# main.net
KiCad netlist of a schematic drawn in Altium Designer
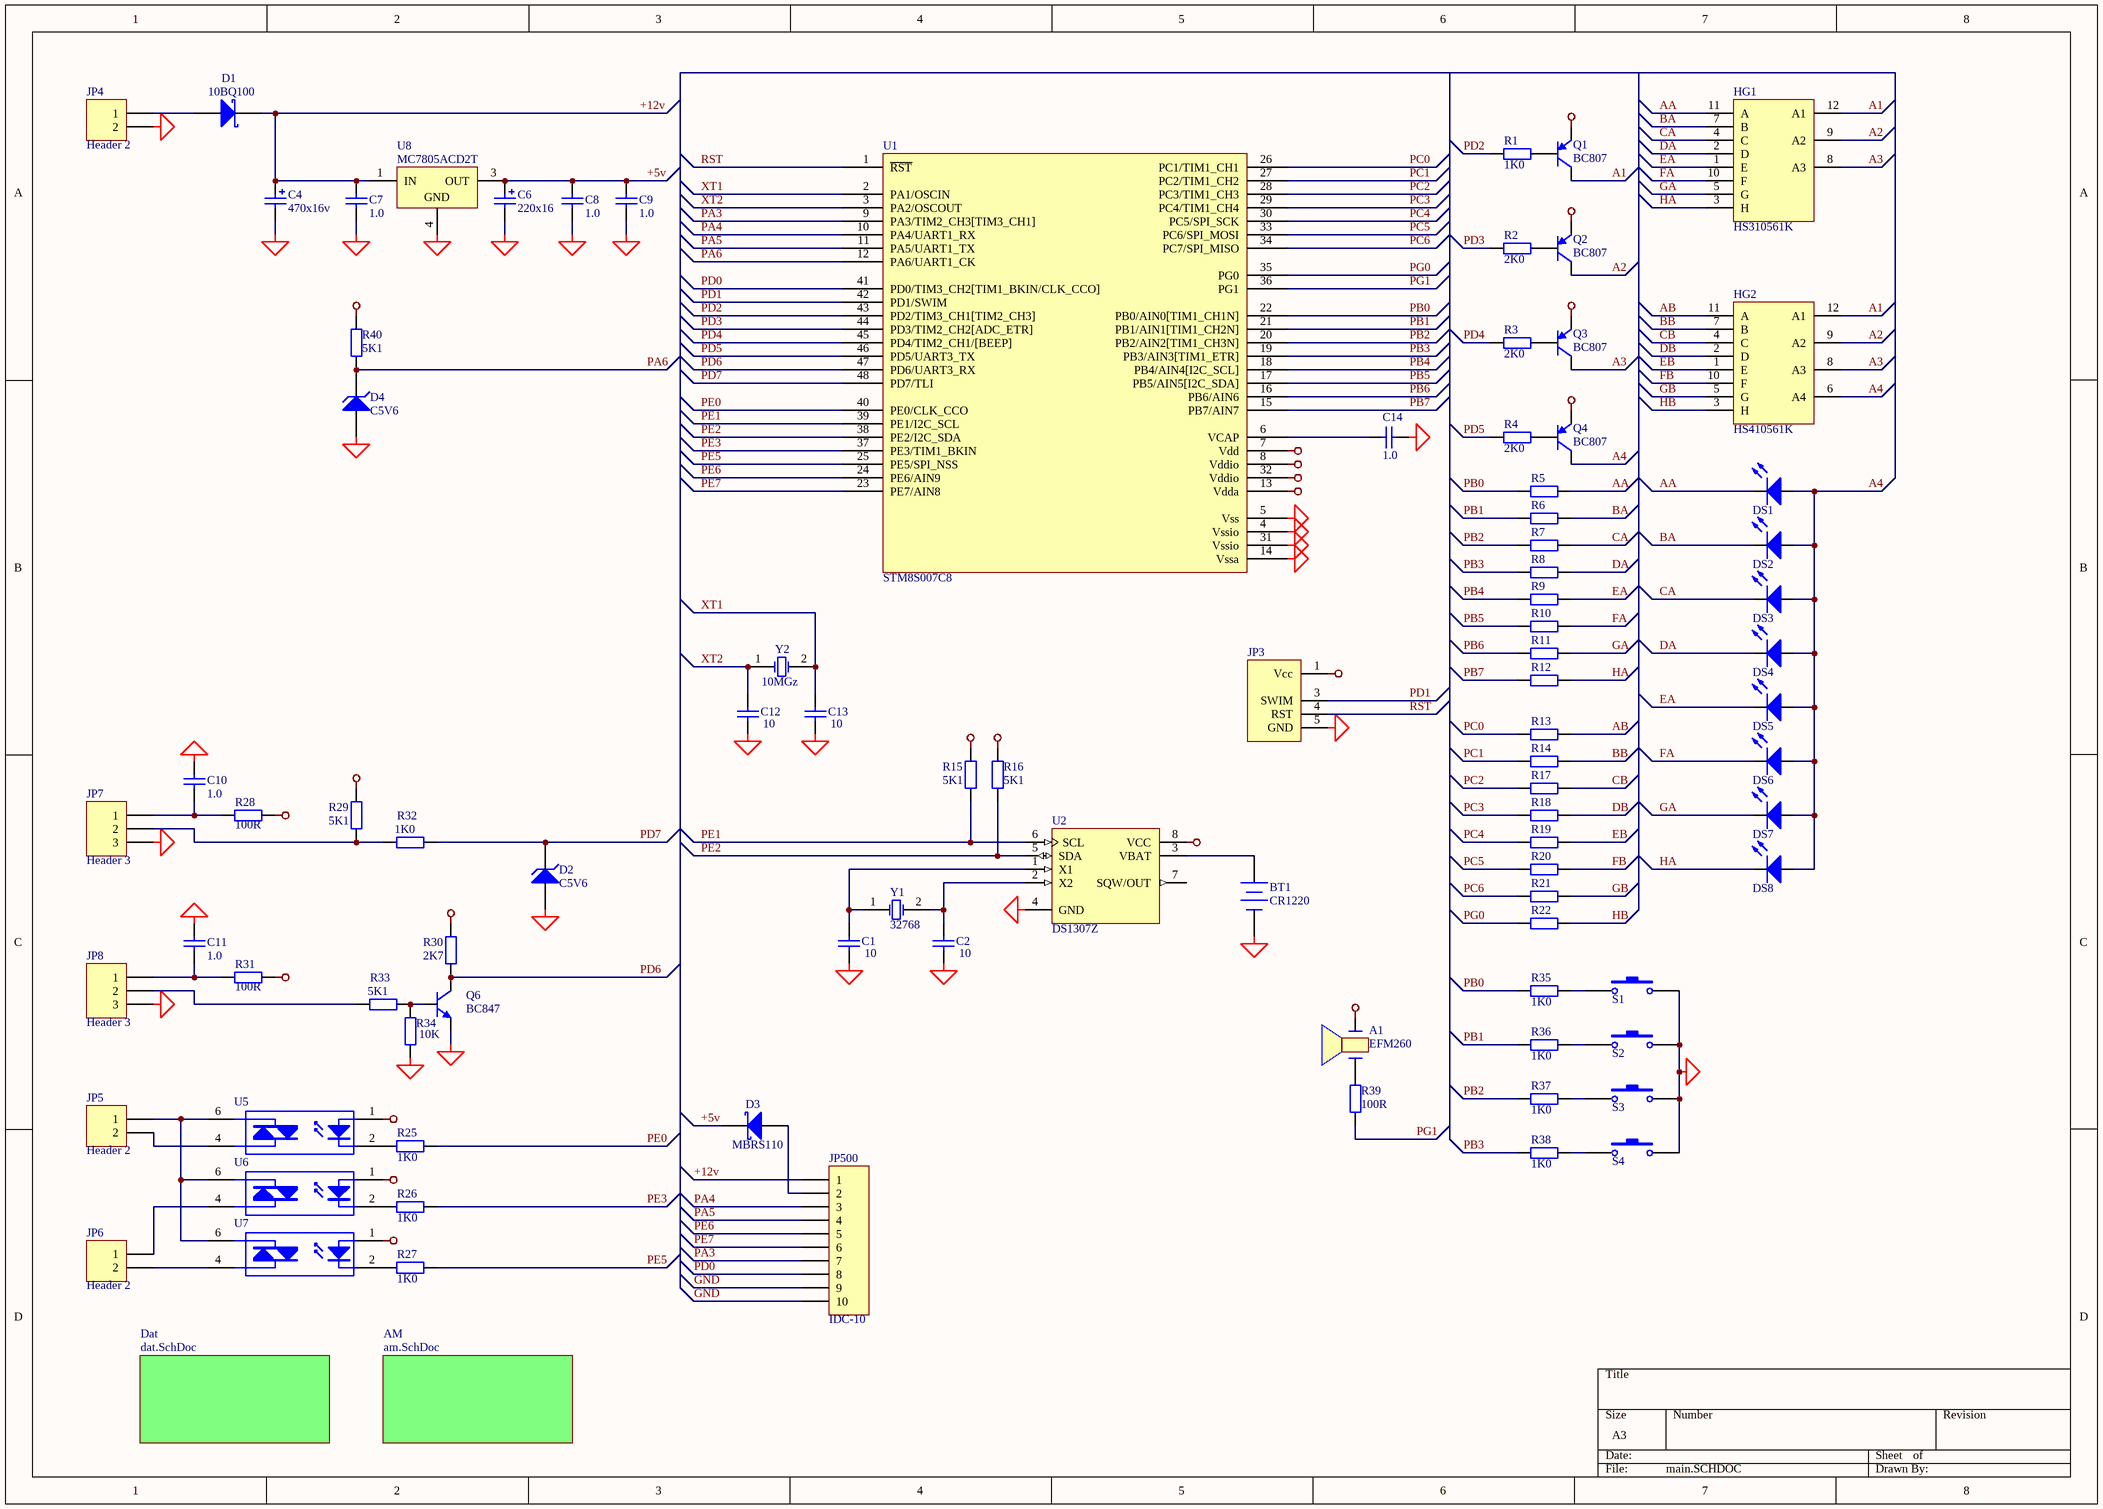
[diagram p0: main.SCHDOC]

(export (version "E")
  (design (tool "Eeschema 10.0.6"))
  (components
    (comp (ref "A1")
      (value "EFM260")
      (footprint "zumm")
      (description "Beeper")
      (libsource (lib "PAL") (part "PJEZ0"))
    )
    (comp (ref "BT1")
      (value "CR1220")
      (footprint "1220_holder")
      (description "Multicell Battery")
      (fields (field (name "MANUFACTURER") "Generic Components") (field (name "PUBLISHER") "Altium Limited"))
      (libsource (lib "Miscellaneous Devices") (part "Battery"))
    )
    (comp (ref "C1")
      (value "10")
      (footprint "_1206")
      (description "Capacitor")
      (fields (field (name "MANUFACTURER") "Generic Components") (field (name "PUBLISHER") "Altium Limited"))
      (libsource (lib "Miscellaneous Devices") (part "Cap Semi"))
    )
    (comp (ref "C2")
      (value "10")
      (footprint "_1206")
      (description "Capacitor")
      (fields (field (name "MANUFACTURER") "Generic Components") (field (name "PUBLISHER") "Altium Limited"))
      (libsource (lib "Miscellaneous Devices") (part "Cap Semi"))
    )
    (comp (ref "C4")
      (value "470x16v")
      (footprint "el5")
      (description "Polarized Capacitor (Radial)")
      (fields (field (name "MANUFACTURER") "Generic Components") (field (name "PUBLISHER") "Altium Limited"))
      (libsource (lib "BUF") (part "Cap Pol1"))
    )
    (comp (ref "C6")
      (value "220x16")
      (footprint "el3")
      (description "Polarized Capacitor (Radial)")
      (fields (field (name "MANUFACTURER") "Generic Components") (field (name "PUBLISHER") "Altium Limited"))
      (libsource (lib "BUF") (part "Cap Pol"))
    )
    (comp (ref "C7")
      (value "Cap")
      (footprint "_1206")
      (description "Capacitor")
      (fields
        (field (name "MANUFACTURER") "Generic Components")
        (field (name "ALTIUM_VALUE") "1.0")
        (field (name "PUBLISHER") "Altium Limited")
      )
      (libsource (lib "BUF") (part "Cap"))
    )
    (comp (ref "C8")
      (value "Cap")
      (footprint "_1206")
      (description "Capacitor")
      (fields
        (field (name "MANUFACTURER") "Generic Components")
        (field (name "ALTIUM_VALUE") "1.0")
        (field (name "PUBLISHER") "Altium Limited")
      )
      (libsource (lib "BUF") (part "Cap"))
    )
    (comp (ref "C9")
      (value "Cap")
      (footprint "_1206")
      (description "Capacitor")
      (fields
        (field (name "MANUFACTURER") "Generic Components")
        (field (name "ALTIUM_VALUE") "1.0")
        (field (name "PUBLISHER") "Altium Limited")
      )
      (libsource (lib "BUF") (part "Cap"))
    )
    (comp (ref "C10")
      (value "Cap")
      (footprint "_1206")
      (description "Capacitor")
      (fields
        (field (name "MANUFACTURER") "Generic Components")
        (field (name "ALTIUM_VALUE") "1.0")
        (field (name "PUBLISHER") "Altium Limited")
      )
      (libsource (lib "BUF") (part "Cap"))
    )
    (comp (ref "C11")
      (value "Cap")
      (footprint "_1206")
      (description "Capacitor")
      (fields
        (field (name "MANUFACTURER") "Generic Components")
        (field (name "ALTIUM_VALUE") "1.0")
        (field (name "PUBLISHER") "Altium Limited")
      )
      (libsource (lib "BUF") (part "Cap"))
    )
    (comp (ref "C12")
      (value "10")
      (footprint "_1206")
      (description "Capacitor")
      (fields (field (name "MANUFACTURER") "Generic Components") (field (name "PUBLISHER") "Altium Limited"))
      (libsource (lib "Miscellaneous Devices") (part "Cap Semi"))
    )
    (comp (ref "C13")
      (value "10")
      (footprint "_1206")
      (description "Capacitor")
      (fields (field (name "MANUFACTURER") "Generic Components") (field (name "PUBLISHER") "Altium Limited"))
      (libsource (lib "Miscellaneous Devices") (part "Cap Semi"))
    )
    (comp (ref "C14")
      (value "1.0")
      (footprint "_1206")
      (description "Capacitor")
      (fields (field (name "MANUFACTURER") "Generic Components") (field (name "PUBLISHER") "Altium Limited"))
      (libsource (lib "Miscellaneous Devices") (part "Cap Semi"))
    )
    (comp (ref "D1")
      (value "10BQ100")
      (footprint "DSO-C2/X2.3")
      (description "Schottky Rectifier")
      (fields
        (field (name "MANUFACTURER") "International Rectifier")
        (field (name "PUBLISHER") "Altium Limited")
      )
      (libsource (lib "IR Discrete Diode") (part "10BQ015"))
    )
    (comp (ref "D2")
      (value "C5V6")
      (footprint "_1206d")
      (description "Zener Diode")
      (fields (field (name "MANUFACTURER") "Generic Components") (field (name "PUBLISHER") "Altium Limited"))
      (libsource (lib "Miscellaneous Devices") (part "D Zener"))
    )
    (comp (ref "D3")
      (value "MBRS110")
      (footprint "DSO-C2/X2.3")
      (description "Schottky Rectifier")
      (fields
        (field (name "MANUFACTURER") "International Rectifier")
        (field (name "PUBLISHER") "Altium Limited")
      )
      (libsource (lib "IR Discrete Diode") (part "10BQ015"))
    )
    (comp (ref "D4")
      (value "C5V6")
      (footprint "_1206d")
      (description "Zener Diode")
      (fields (field (name "MANUFACTURER") "Generic Components") (field (name "PUBLISHER") "Altium Limited"))
      (libsource (lib "Miscellaneous Devices") (part "D Zener"))
    )
    (comp (ref "DS1")
      (value "LED0")
      (footprint "el3")
      (description "Typical INFRARED GaAs LED")
      (fields (field (name "MANUFACTURER") "Generic Components") (field (name "PUBLISHER") "Altium Limited"))
      (libsource (lib "PAL") (part "LED0"))
    )
    (comp (ref "DS2")
      (value "LED0")
      (footprint "el3")
      (description "Typical INFRARED GaAs LED")
      (fields (field (name "MANUFACTURER") "Generic Components") (field (name "PUBLISHER") "Altium Limited"))
      (libsource (lib "PAL") (part "LED0"))
    )
    (comp (ref "DS3")
      (value "LED0")
      (footprint "el3")
      (description "Typical INFRARED GaAs LED")
      (fields (field (name "MANUFACTURER") "Generic Components") (field (name "PUBLISHER") "Altium Limited"))
      (libsource (lib "PAL") (part "LED0"))
    )
    (comp (ref "DS4")
      (value "LED0")
      (footprint "el3")
      (description "Typical INFRARED GaAs LED")
      (fields (field (name "MANUFACTURER") "Generic Components") (field (name "PUBLISHER") "Altium Limited"))
      (libsource (lib "PAL") (part "LED0"))
    )
    (comp (ref "DS5")
      (value "LED0")
      (footprint "el3")
      (description "Typical INFRARED GaAs LED")
      (fields (field (name "MANUFACTURER") "Generic Components") (field (name "PUBLISHER") "Altium Limited"))
      (libsource (lib "PAL") (part "LED0"))
    )
    (comp (ref "DS6")
      (value "LED0")
      (footprint "el3")
      (description "Typical INFRARED GaAs LED")
      (fields (field (name "MANUFACTURER") "Generic Components") (field (name "PUBLISHER") "Altium Limited"))
      (libsource (lib "PAL") (part "LED0"))
    )
    (comp (ref "DS7")
      (value "LED0")
      (footprint "el3")
      (description "Typical INFRARED GaAs LED")
      (fields (field (name "MANUFACTURER") "Generic Components") (field (name "PUBLISHER") "Altium Limited"))
      (libsource (lib "PAL") (part "LED0"))
    )
    (comp (ref "DS8")
      (value "LED0")
      (footprint "el3")
      (description "Typical INFRARED GaAs LED")
      (fields (field (name "MANUFACTURER") "Generic Components") (field (name "PUBLISHER") "Altium Limited"))
      (libsource (lib "PAL") (part "LED0"))
    )
    (comp (ref "HG1") (value "HS310561K") (footprint "HS310561K") (libsource (lib "PAL") (part "HS310561K")))
    (comp (ref "HG2") (value "HS410561K") (footprint "HS410561K") (libsource (lib "PAL") (part "HS410561K")))
    (comp (ref "JP3") (value "~") (footprint "HDR1X5_uart") (libsource (lib "PAL") (part "SWIM_CONN")))
    (comp (ref "JP4")
      (value "Header 2")
      (footprint "BT5-2")
      (description "Header, 2-Pin")
      (fields (field (name "MANUFACTURER") "Generic Components") (field (name "PUBLISHER") "Altium Limited"))
      (libsource (lib "Miscellaneous Connectors") (part "Header 2"))
    )
    (comp (ref "JP5")
      (value "Header 2")
      (footprint "BT5-2")
      (description "Header, 2-Pin")
      (fields (field (name "MANUFACTURER") "Generic Components") (field (name "PUBLISHER") "Altium Limited"))
      (libsource (lib "Miscellaneous Connectors") (part "Header 2"))
    )
    (comp (ref "JP6")
      (value "Header 2")
      (footprint "BT5-2")
      (description "Header, 2-Pin")
      (fields (field (name "MANUFACTURER") "Generic Components") (field (name "PUBLISHER") "Altium Limited"))
      (libsource (lib "Miscellaneous Connectors") (part "Header 2"))
    )
    (comp (ref "JP7")
      (value "Header 3")
      (footprint "BT5-3")
      (description "Header, 3-Pin")
      (fields (field (name "MANUFACTURER") "Generic Components") (field (name "PUBLISHER") "Altium Limited"))
      (libsource (lib "Miscellaneous Connectors") (part "Header 3"))
    )
    (comp (ref "JP8")
      (value "Header 3")
      (footprint "BT5-3")
      (description "Header, 3-Pin")
      (fields (field (name "MANUFACTURER") "Generic Components") (field (name "PUBLISHER") "Altium Limited"))
      (libsource (lib "Miscellaneous Connectors") (part "Header 3"))
    )
    (comp (ref "JP500")
      (value "IDC-10")
      (footprint "HDR2X5")
      (description "Header, 10-Pin")
      (fields (field (name "MANUFACTURER") "Generic Components") (field (name "PUBLISHER") "Altium Limited"))
      (libsource (lib "Miscellaneous Connectors") (part "Header 10"))
    )
    (comp (ref "Q1")
      (value "BC807")
      (footprint "SO-G3")
      (description "General Purpose Transistor PNP Silicon")
      (fields (field (name "MANUFACTURER") "Motorola") (field (name "PUBLISHER") "Altium Limited"))
      (libsource (lib "PAL") (part "BC857ALT1"))
    )
    (comp (ref "Q2")
      (value "BC807")
      (footprint "SO-G3")
      (description "General Purpose Transistor PNP Silicon")
      (fields (field (name "MANUFACTURER") "Motorola") (field (name "PUBLISHER") "Altium Limited"))
      (libsource (lib "PAL") (part "BC857ALT1"))
    )
    (comp (ref "Q3")
      (value "BC807")
      (footprint "SO-G3")
      (description "General Purpose Transistor PNP Silicon")
      (fields (field (name "MANUFACTURER") "Motorola") (field (name "PUBLISHER") "Altium Limited"))
      (libsource (lib "PAL") (part "BC857ALT1"))
    )
    (comp (ref "Q4")
      (value "BC807")
      (footprint "SO-G3")
      (description "General Purpose Transistor PNP Silicon")
      (fields (field (name "MANUFACTURER") "Motorola") (field (name "PUBLISHER") "Altium Limited"))
      (libsource (lib "PAL") (part "BC857ALT1"))
    )
    (comp (ref "Q6")
      (value "BC847")
      (footprint "SO-G3")
      (description "General Purpose Transistor NPN Silicon")
      (fields (field (name "MANUFACTURER") "Motorola") (field (name "PUBLISHER") "Altium Limited"))
      (libsource (lib "PAL") (part "BC847ALT1"))
    )
    (comp (ref "R1")
      (value "Res2")
      (footprint "_1206")
      (description "Resistor")
      (fields
        (field (name "MANUFACTURER") "Generic Components")
        (field (name "ALTIUM_VALUE") "1K0")
        (field (name "PUBLISHER") "Altium Limited")
      )
      (libsource (lib "") (part "Res2_1"))
    )
    (comp (ref "R2")
      (value "Res2")
      (footprint "_1206")
      (description "Resistor")
      (fields
        (field (name "MANUFACTURER") "Generic Components")
        (field (name "ALTIUM_VALUE") "2K0")
        (field (name "PUBLISHER") "Altium Limited")
      )
      (libsource (lib "") (part "Res2_1"))
    )
    (comp (ref "R3")
      (value "Res2")
      (footprint "_1206")
      (description "Resistor")
      (fields
        (field (name "MANUFACTURER") "Generic Components")
        (field (name "ALTIUM_VALUE") "2K0")
        (field (name "PUBLISHER") "Altium Limited")
      )
      (libsource (lib "") (part "Res2_1"))
    )
    (comp (ref "R4")
      (value "Res2")
      (footprint "_1206")
      (description "Resistor")
      (fields
        (field (name "MANUFACTURER") "Generic Components")
        (field (name "ALTIUM_VALUE") "2K0")
        (field (name "PUBLISHER") "Altium Limited")
      )
      (libsource (lib "") (part "Res2_1"))
    )
    (comp (ref "R5")
      (value "Res2")
      (footprint "_1206")
      (description "Resistor")
      (fields (field (name "MANUFACTURER") "Generic Components") (field (name "PUBLISHER") "Altium Limited"))
      (libsource (lib "") (part "Res2_1"))
    )
    (comp (ref "R6")
      (value "Res2")
      (footprint "_1206")
      (description "Resistor")
      (fields (field (name "MANUFACTURER") "Generic Components") (field (name "PUBLISHER") "Altium Limited"))
      (libsource (lib "") (part "Res2_1"))
    )
    (comp (ref "R7")
      (value "Res2")
      (footprint "_1206")
      (description "Resistor")
      (fields (field (name "MANUFACTURER") "Generic Components") (field (name "PUBLISHER") "Altium Limited"))
      (libsource (lib "") (part "Res2_1"))
    )
    (comp (ref "R8")
      (value "Res2")
      (footprint "_1206")
      (description "Resistor")
      (fields (field (name "MANUFACTURER") "Generic Components") (field (name "PUBLISHER") "Altium Limited"))
      (libsource (lib "") (part "Res2_1"))
    )
    (comp (ref "R9")
      (value "Res2")
      (footprint "_1206")
      (description "Resistor")
      (fields (field (name "MANUFACTURER") "Generic Components") (field (name "PUBLISHER") "Altium Limited"))
      (libsource (lib "") (part "Res2_1"))
    )
    (comp (ref "R10")
      (value "Res2")
      (footprint "_1206")
      (description "Resistor")
      (fields (field (name "MANUFACTURER") "Generic Components") (field (name "PUBLISHER") "Altium Limited"))
      (libsource (lib "") (part "Res2_1"))
    )
    (comp (ref "R11")
      (value "Res2")
      (footprint "_1206")
      (description "Resistor")
      (fields (field (name "MANUFACTURER") "Generic Components") (field (name "PUBLISHER") "Altium Limited"))
      (libsource (lib "") (part "Res2_1"))
    )
    (comp (ref "R12")
      (value "Res2")
      (footprint "_1206")
      (description "Resistor")
      (fields (field (name "MANUFACTURER") "Generic Components") (field (name "PUBLISHER") "Altium Limited"))
      (libsource (lib "") (part "Res2_1"))
    )
    (comp (ref "R13")
      (value "Res2")
      (footprint "_1206")
      (description "Resistor")
      (fields (field (name "MANUFACTURER") "Generic Components") (field (name "PUBLISHER") "Altium Limited"))
      (libsource (lib "") (part "Res2_1"))
    )
    (comp (ref "R14")
      (value "Res2")
      (footprint "_1206")
      (description "Resistor")
      (fields (field (name "MANUFACTURER") "Generic Components") (field (name "PUBLISHER") "Altium Limited"))
      (libsource (lib "") (part "Res2_1"))
    )
    (comp (ref "R15")
      (value "Res2")
      (footprint "_1206")
      (description "Resistor")
      (fields
        (field (name "MANUFACTURER") "Generic Components")
        (field (name "ALTIUM_VALUE") "5K1")
        (field (name "PUBLISHER") "Altium Limited")
      )
      (libsource (lib "Miscellaneous Devices") (part "Res2"))
    )
    (comp (ref "R16")
      (value "Res2")
      (footprint "_1206")
      (description "Resistor")
      (fields
        (field (name "MANUFACTURER") "Generic Components")
        (field (name "ALTIUM_VALUE") "5K1")
        (field (name "PUBLISHER") "Altium Limited")
      )
      (libsource (lib "Miscellaneous Devices") (part "Res2"))
    )
    (comp (ref "R17")
      (value "Res2")
      (footprint "_1206")
      (description "Resistor")
      (fields (field (name "MANUFACTURER") "Generic Components") (field (name "PUBLISHER") "Altium Limited"))
      (libsource (lib "") (part "Res2_1"))
    )
    (comp (ref "R18")
      (value "Res2")
      (footprint "_1206")
      (description "Resistor")
      (fields (field (name "MANUFACTURER") "Generic Components") (field (name "PUBLISHER") "Altium Limited"))
      (libsource (lib "") (part "Res2_1"))
    )
    (comp (ref "R19")
      (value "Res2")
      (footprint "_1206")
      (description "Resistor")
      (fields (field (name "MANUFACTURER") "Generic Components") (field (name "PUBLISHER") "Altium Limited"))
      (libsource (lib "") (part "Res2_1"))
    )
    (comp (ref "R20")
      (value "Res2")
      (footprint "_1206")
      (description "Resistor")
      (fields (field (name "MANUFACTURER") "Generic Components") (field (name "PUBLISHER") "Altium Limited"))
      (libsource (lib "") (part "Res2_1"))
    )
    (comp (ref "R21")
      (value "Res2")
      (footprint "_1206")
      (description "Resistor")
      (fields (field (name "MANUFACTURER") "Generic Components") (field (name "PUBLISHER") "Altium Limited"))
      (libsource (lib "") (part "Res2_1"))
    )
    (comp (ref "R22")
      (value "Res2")
      (footprint "_1206")
      (description "Resistor")
      (fields (field (name "MANUFACTURER") "Generic Components") (field (name "PUBLISHER") "Altium Limited"))
      (libsource (lib "") (part "Res2_1"))
    )
    (comp (ref "R25")
      (value "Res2")
      (footprint "_1206")
      (description "Resistor")
      (fields
        (field (name "MANUFACTURER") "Generic Components")
        (field (name "ALTIUM_VALUE") "1K0")
        (field (name "PUBLISHER") "Altium Limited")
      )
      (libsource (lib "") (part "Res2_2"))
    )
    (comp (ref "R26")
      (value "Res2")
      (footprint "_1206")
      (description "Resistor")
      (fields
        (field (name "MANUFACTURER") "Generic Components")
        (field (name "ALTIUM_VALUE") "1K0")
        (field (name "PUBLISHER") "Altium Limited")
      )
      (libsource (lib "") (part "Res2_2"))
    )
    (comp (ref "R27")
      (value "Res2")
      (footprint "_1206")
      (description "Resistor")
      (fields
        (field (name "MANUFACTURER") "Generic Components")
        (field (name "ALTIUM_VALUE") "1K0")
        (field (name "PUBLISHER") "Altium Limited")
      )
      (libsource (lib "") (part "Res2_2"))
    )
    (comp (ref "R28")
      (value "Res2")
      (footprint "_1206")
      (description "Resistor")
      (fields
        (field (name "MANUFACTURER") "Generic Components")
        (field (name "ALTIUM_VALUE") "100R")
        (field (name "PUBLISHER") "Altium Limited")
      )
      (libsource (lib "") (part "Res2_2"))
    )
    (comp (ref "R29")
      (value "Res2")
      (footprint "_1206")
      (description "Resistor")
      (fields
        (field (name "MANUFACTURER") "Generic Components")
        (field (name "ALTIUM_VALUE") "5K1")
        (field (name "PUBLISHER") "Altium Limited")
      )
      (libsource (lib "Miscellaneous Devices") (part "Res2"))
    )
    (comp (ref "R30")
      (value "Res2")
      (footprint "_1206")
      (description "Resistor")
      (fields
        (field (name "MANUFACTURER") "Generic Components")
        (field (name "ALTIUM_VALUE") "2K7")
        (field (name "PUBLISHER") "Altium Limited")
      )
      (libsource (lib "Miscellaneous Devices") (part "Res2"))
    )
    (comp (ref "R31")
      (value "Res2")
      (footprint "_1206")
      (description "Resistor")
      (fields
        (field (name "MANUFACTURER") "Generic Components")
        (field (name "ALTIUM_VALUE") "100R")
        (field (name "PUBLISHER") "Altium Limited")
      )
      (libsource (lib "") (part "Res2_2"))
    )
    (comp (ref "R32")
      (value "1K0")
      (footprint "_1206")
      (description "Resistor")
      (fields (field (name "MANUFACTURER") "Generic Components") (field (name "PUBLISHER") "Altium Limited"))
      (libsource (lib "") (part "Res2_1"))
    )
    (comp (ref "R33")
      (value "5K1")
      (footprint "_1206")
      (description "Resistor")
      (fields (field (name "MANUFACTURER") "Generic Components") (field (name "PUBLISHER") "Altium Limited"))
      (libsource (lib "") (part "Res2_1"))
    )
    (comp (ref "R34")
      (value "10K")
      (footprint "_1206")
      (description "Resistor")
      (fields (field (name "MANUFACTURER") "Generic Components") (field (name "PUBLISHER") "Altium Limited"))
      (libsource (lib "") (part "Res2_3"))
    )
    (comp (ref "R35")
      (value "Res2")
      (footprint "_1206")
      (description "Resistor")
      (fields
        (field (name "MANUFACTURER") "Generic Components")
        (field (name "ALTIUM_VALUE") "1K0")
        (field (name "PUBLISHER") "Altium Limited")
      )
      (libsource (lib "") (part "Res2_1"))
    )
    (comp (ref "R36")
      (value "Res2")
      (footprint "_1206")
      (description "Resistor")
      (fields
        (field (name "MANUFACTURER") "Generic Components")
        (field (name "ALTIUM_VALUE") "1K0")
        (field (name "PUBLISHER") "Altium Limited")
      )
      (libsource (lib "") (part "Res2_1"))
    )
    (comp (ref "R37")
      (value "Res2")
      (footprint "_1206")
      (description "Resistor")
      (fields
        (field (name "MANUFACTURER") "Generic Components")
        (field (name "ALTIUM_VALUE") "1K0")
        (field (name "PUBLISHER") "Altium Limited")
      )
      (libsource (lib "") (part "Res2_1"))
    )
    (comp (ref "R38")
      (value "Res2")
      (footprint "_1206")
      (description "Resistor")
      (fields
        (field (name "MANUFACTURER") "Generic Components")
        (field (name "ALTIUM_VALUE") "1K0")
        (field (name "PUBLISHER") "Altium Limited")
      )
      (libsource (lib "") (part "Res2_1"))
    )
    (comp (ref "R39")
      (value "Res2")
      (footprint "_1206")
      (description "Resistor")
      (fields
        (field (name "MANUFACTURER") "Generic Components")
        (field (name "ALTIUM_VALUE") "100R")
        (field (name "PUBLISHER") "Altium Limited")
      )
      (libsource (lib "Miscellaneous Devices") (part "Res2"))
    )
    (comp (ref "R40")
      (value "5K1")
      (footprint "_1206")
      (description "Resistor")
      (fields (field (name "MANUFACTURER") "Generic Components") (field (name "PUBLISHER") "Altium Limited"))
      (libsource (lib "Miscellaneous Devices") (part "Res2"))
    )
    (comp (ref "S1")
      (value "SWT-6")
      (footprint "SWT-6")
      (description "Switch")
      (fields (field (name "MANUFACTURER") "Generic Components") (field (name "PUBLISHER") "Altium Limited"))
      (libsource (lib "PAL") (part "SWT-6"))
    )
    (comp (ref "S2")
      (value "SWT-6")
      (footprint "SWT-6")
      (description "Switch")
      (fields (field (name "MANUFACTURER") "Generic Components") (field (name "PUBLISHER") "Altium Limited"))
      (libsource (lib "PAL") (part "SWT-6"))
    )
    (comp (ref "S3")
      (value "SWT-6")
      (footprint "SWT-6")
      (description "Switch")
      (fields (field (name "MANUFACTURER") "Generic Components") (field (name "PUBLISHER") "Altium Limited"))
      (libsource (lib "PAL") (part "SWT-6"))
    )
    (comp (ref "S4")
      (value "SWT-6")
      (footprint "SWT-6")
      (description "Switch")
      (fields (field (name "MANUFACTURER") "Generic Components") (field (name "PUBLISHER") "Altium Limited"))
      (libsource (lib "PAL") (part "SWT-6"))
    )
    (comp (ref "U1")
      (value "STM8S007C8")
      (footprint "F-QFP7X7-G48/X.3N")
      (libsource (lib "PAL") (part "STM8S007C8"))
    )
    (comp (ref "U2")
      (value "DS1307Z")
      (footprint "SO-G8/Z7.45")
      (description "64 X 8 Serial Real-Time Clock")
      (fields
        (field (name "MANUFACTURER") "Dallas Semiconductor")
        (field (name "PUBLISHER") "Altium Limited")
      )
      (libsource (lib "Dallas Peripheral Real Time Clock") (part "DS1307Z"))
    )
    (comp (ref "U5")
      (value "Opto TRIAC")
      (footprint "DIP-6")
      (description "Opto-Triac")
      (fields (field (name "MANUFACTURER") "Generic Components") (field (name "PUBLISHER") "Altium Limited"))
      (libsource (lib "PAL") (part "Opto TRIAC"))
    )
    (comp (ref "U6")
      (value "Opto TRIAC")
      (footprint "DIP-6")
      (description "Opto-Triac")
      (fields (field (name "MANUFACTURER") "Generic Components") (field (name "PUBLISHER") "Altium Limited"))
      (libsource (lib "PAL") (part "Opto TRIAC"))
    )
    (comp (ref "U7")
      (value "Opto TRIAC")
      (footprint "DIP-6")
      (description "Opto-Triac")
      (fields (field (name "MANUFACTURER") "Generic Components") (field (name "PUBLISHER") "Altium Limited"))
      (libsource (lib "PAL") (part "Opto TRIAC"))
    )
    (comp (ref "U8")
      (value "MC7805ACD2T")
      (footprint "D2PAK")
      (description "Three-Terminal Positive Voltage Regulator")
      (fields (field (name "MANUFACTURER") "ON Semiconductor") (field (name "PUBLISHER") "Altium Limited"))
      (libsource (lib "ON Semi Power Mgt Voltage Regulator") (part "MC7805ACD2T"))
    )
    (comp (ref "Y1")
      (value "32768")
      (footprint "BCY-W2/D3.1")
      (description "Crystal Oscillator")
      (fields (field (name "MANUFACTURER") "Generic Components") (field (name "PUBLISHER") "Altium Limited"))
      (libsource (lib "Miscellaneous Devices") (part "XTAL"))
    )
    (comp (ref "Y2")
      (value "10MGz")
      (footprint "qwarz1")
      (description "Crystal Oscillator")
      (fields (field (name "MANUFACTURER") "Generic Components") (field (name "PUBLISHER") "Altium Limited"))
      (libsource (lib "Miscellaneous Devices") (part "XTAL"))
    )
  )
  (nets
    (net (code "1") (name "+5v") (class "Default")
      (node (ref "A1") (pin "1") (pinfunction "1_1") (pintype "passive"))
      (node (ref "C6") (pin "1") (pinfunction "1_1") (pintype "passive"))
      (node (ref "C8") (pin "2") (pinfunction "2_2") (pintype "passive"))
      (node (ref "C9") (pin "2") (pinfunction "2_2") (pintype "passive"))
      (node (ref "D3") (pin "2") (pinfunction "K_2") (pintype "passive"))
      (node (ref "JP3") (pin "1") (pinfunction "Vcc_1") (pintype "passive"))
      (node (ref "Q1") (pin "2") (pinfunction "E_2") (pintype "passive"))
      (node (ref "Q2") (pin "2") (pinfunction "E_2") (pintype "passive"))
      (node (ref "Q3") (pin "2") (pinfunction "E_2") (pintype "passive"))
      (node (ref "Q4") (pin "2") (pinfunction "E_2") (pintype "passive"))
      (node (ref "R15") (pin "1") (pinfunction "1_1") (pintype "passive"))
      (node (ref "R16") (pin "1") (pinfunction "1_1") (pintype "passive"))
      (node (ref "R28") (pin "2") (pinfunction "2_2") (pintype "passive"))
      (node (ref "R29") (pin "1") (pinfunction "1_1") (pintype "passive"))
      (node (ref "R30") (pin "1") (pinfunction "1_1") (pintype "passive"))
      (node (ref "R31") (pin "2") (pinfunction "2_2") (pintype "passive"))
      (node (ref "U1") (pin "13") (pinfunction "Vdda_13") (pintype "passive"))
      (node (ref "U1") (pin "32") (pinfunction "Vddio_32") (pintype "passive"))
      (node (ref "U1") (pin "7") (pinfunction "Vdd_7") (pintype "passive"))
      (node (ref "U1") (pin "8") (pinfunction "Vddio_8") (pintype "passive"))
      (node (ref "U2") (pin "8") (pinfunction "VCC_8") (pintype "power_in"))
      (node (ref "U5") (pin "1") (pinfunction "A_1") (pintype "passive"))
      (node (ref "U6") (pin "1") (pinfunction "A_1") (pintype "passive"))
      (node (ref "U7") (pin "1") (pinfunction "A_1") (pintype "passive"))
      (node (ref "U8") (pin "3") (pinfunction "OUT_3") (pintype "power_in"))
    )
    (net (code "2") (name "+12v") (class "Default")
      (node (ref "C4") (pin "1") (pinfunction "1_1") (pintype "passive"))
      (node (ref "C7") (pin "2") (pinfunction "2_2") (pintype "passive"))
      (node (ref "D1") (pin "2") (pinfunction "K_2") (pintype "passive"))
      (node (ref "JP500") (pin "1") (pinfunction "1_1") (pintype "passive"))
      (node (ref "R40") (pin "1") (pinfunction "1_1") (pintype "passive"))
      (node (ref "U8") (pin "1") (pinfunction "IN_1") (pintype "power_in"))
    )
    (net (code "3") (name "/A1") (class "Default")
      (node (ref "HG1") (pin "12") (pinfunction "A1_12") (pintype "passive"))
      (node (ref "HG2") (pin "12") (pinfunction "A1_12") (pintype "passive"))
      (node (ref "Q1") (pin "3") (pinfunction "C_3") (pintype "passive"))
    )
    (net (code "4") (name "/A2") (class "Default")
      (node (ref "HG1") (pin "9") (pinfunction "A2_9") (pintype "passive"))
      (node (ref "HG2") (pin "9") (pinfunction "A2_9") (pintype "passive"))
      (node (ref "Q2") (pin "3") (pinfunction "C_3") (pintype "passive"))
    )
    (net (code "5") (name "/A3") (class "Default")
      (node (ref "HG1") (pin "8") (pinfunction "A3_8") (pintype "passive"))
      (node (ref "HG2") (pin "8") (pinfunction "A3_8") (pintype "passive"))
      (node (ref "Q3") (pin "3") (pinfunction "C_3") (pintype "passive"))
    )
    (net (code "6") (name "/A4") (class "Default")
      (node (ref "DS1") (pin "1") (pinfunction "A_1") (pintype "passive"))
      (node (ref "DS2") (pin "1") (pinfunction "A_1") (pintype "passive"))
      (node (ref "DS3") (pin "1") (pinfunction "A_1") (pintype "passive"))
      (node (ref "DS4") (pin "1") (pinfunction "A_1") (pintype "passive"))
      (node (ref "DS5") (pin "1") (pinfunction "A_1") (pintype "passive"))
      (node (ref "DS6") (pin "1") (pinfunction "A_1") (pintype "passive"))
      (node (ref "DS7") (pin "1") (pinfunction "A_1") (pintype "passive"))
      (node (ref "DS8") (pin "1") (pinfunction "A_1") (pintype "passive"))
      (node (ref "HG2") (pin "6") (pinfunction "A4_6") (pintype "passive"))
      (node (ref "Q4") (pin "3") (pinfunction "C_3") (pintype "passive"))
    )
    (net (code "7") (name "/AA") (class "Default")
      (node (ref "DS1") (pin "2") (pinfunction "K_2") (pintype "passive"))
      (node (ref "HG1") (pin "11") (pinfunction "A_11") (pintype "passive"))
      (node (ref "R5") (pin "1") (pinfunction "1_1") (pintype "passive"))
    )
    (net (code "8") (name "/AB") (class "Default")
      (node (ref "HG2") (pin "11") (pinfunction "A_11") (pintype "passive"))
      (node (ref "R13") (pin "1") (pinfunction "1_1") (pintype "passive"))
    )
    (net (code "9") (name "/BA") (class "Default")
      (node (ref "DS2") (pin "2") (pinfunction "K_2") (pintype "passive"))
      (node (ref "HG1") (pin "7") (pinfunction "B_7") (pintype "passive"))
      (node (ref "R6") (pin "1") (pinfunction "1_1") (pintype "passive"))
    )
    (net (code "10") (name "/BB") (class "Default")
      (node (ref "HG2") (pin "7") (pinfunction "B_7") (pintype "passive"))
      (node (ref "R14") (pin "1") (pinfunction "1_1") (pintype "passive"))
    )
    (net (code "11") (name "/CA") (class "Default")
      (node (ref "DS3") (pin "2") (pinfunction "K_2") (pintype "passive"))
      (node (ref "HG1") (pin "4") (pinfunction "C_4") (pintype "passive"))
      (node (ref "R7") (pin "1") (pinfunction "1_1") (pintype "passive"))
    )
    (net (code "12") (name "/CB") (class "Default")
      (node (ref "HG2") (pin "4") (pinfunction "C_4") (pintype "passive"))
      (node (ref "R17") (pin "1") (pinfunction "1_1") (pintype "passive"))
    )
    (net (code "13") (name "/DA") (class "Default")
      (node (ref "DS4") (pin "2") (pinfunction "K_2") (pintype "passive"))
      (node (ref "HG1") (pin "2") (pinfunction "D_2") (pintype "passive"))
      (node (ref "R8") (pin "1") (pinfunction "1_1") (pintype "passive"))
    )
    (net (code "14") (name "/DB") (class "Default")
      (node (ref "HG2") (pin "2") (pinfunction "D_2") (pintype "passive"))
      (node (ref "R18") (pin "1") (pinfunction "1_1") (pintype "passive"))
    )
    (net (code "15") (name "/EA") (class "Default")
      (node (ref "DS5") (pin "2") (pinfunction "K_2") (pintype "passive"))
      (node (ref "HG1") (pin "1") (pinfunction "E_1") (pintype "passive"))
      (node (ref "R9") (pin "1") (pinfunction "1_1") (pintype "passive"))
    )
    (net (code "16") (name "/EB") (class "Default")
      (node (ref "HG2") (pin "1") (pinfunction "E_1") (pintype "passive"))
      (node (ref "R19") (pin "1") (pinfunction "1_1") (pintype "passive"))
    )
    (net (code "17") (name "/FA") (class "Default")
      (node (ref "DS6") (pin "2") (pinfunction "K_2") (pintype "passive"))
      (node (ref "HG1") (pin "10") (pinfunction "F_10") (pintype "passive"))
      (node (ref "R10") (pin "1") (pinfunction "1_1") (pintype "passive"))
    )
    (net (code "18") (name "/FB") (class "Default")
      (node (ref "HG2") (pin "10") (pinfunction "F_10") (pintype "passive"))
      (node (ref "R20") (pin "1") (pinfunction "1_1") (pintype "passive"))
    )
    (net (code "19") (name "/GA") (class "Default")
      (node (ref "DS7") (pin "2") (pinfunction "K_2") (pintype "passive"))
      (node (ref "HG1") (pin "5") (pinfunction "G_5") (pintype "passive"))
      (node (ref "R11") (pin "1") (pinfunction "1_1") (pintype "passive"))
    )
    (net (code "20") (name "/GB") (class "Default")
      (node (ref "HG2") (pin "5") (pinfunction "G_5") (pintype "passive"))
      (node (ref "R21") (pin "1") (pinfunction "1_1") (pintype "passive"))
    )
    (net (code "21") (name "/HA") (class "Default")
      (node (ref "DS8") (pin "2") (pinfunction "K_2") (pintype "passive"))
      (node (ref "HG1") (pin "3") (pinfunction "H_3") (pintype "passive"))
      (node (ref "R12") (pin "1") (pinfunction "1_1") (pintype "passive"))
    )
    (net (code "22") (name "/HB") (class "Default")
      (node (ref "HG2") (pin "3") (pinfunction "H_3") (pintype "passive"))
      (node (ref "R22") (pin "1") (pinfunction "1_1") (pintype "passive"))
    )
    (net (code "23") (name "/PA3") (class "Default")
      (node (ref "JP500") (pin "7") (pinfunction "7_7") (pintype "passive"))
      (node (ref "U1") (pin "9") (pinfunction "PA3/TIM2_CH3[TIM3_CH1]_9") (pintype "passive"))
    )
    (net (code "24") (name "/PA4") (class "Default")
      (node (ref "JP500") (pin "3") (pinfunction "3_3") (pintype "passive"))
      (node (ref "U1") (pin "10") (pinfunction "PA4/UART1_RX_10") (pintype "passive"))
    )
    (net (code "25") (name "/PA5") (class "Default")
      (node (ref "JP500") (pin "4") (pinfunction "4_4") (pintype "passive"))
      (node (ref "U1") (pin "11") (pinfunction "PA5/UART1_TX_11") (pintype "passive"))
    )
    (net (code "26") (name "/PA6") (class "Default")
      (node (ref "D4") (pin "2") (pinfunction "K_2") (pintype "passive"))
      (node (ref "R40") (pin "2") (pinfunction "2_2") (pintype "passive"))
      (node (ref "U1") (pin "12") (pinfunction "PA6/UART1_CK_12") (pintype "passive"))
    )
    (net (code "27") (name "/PB0") (class "Default")
      (node (ref "R35") (pin "2") (pinfunction "2_2") (pintype "passive"))
      (node (ref "R5") (pin "2") (pinfunction "2_2") (pintype "passive"))
      (node (ref "U1") (pin "22") (pinfunction "PB0/AIN0[TIM1_CH1N]_22") (pintype "passive"))
    )
    (net (code "28") (name "/PB1") (class "Default")
      (node (ref "R36") (pin "2") (pinfunction "2_2") (pintype "passive"))
      (node (ref "R6") (pin "2") (pinfunction "2_2") (pintype "passive"))
      (node (ref "U1") (pin "21") (pinfunction "PB1/AIN1[TIM1_CH2N]_21") (pintype "passive"))
    )
    (net (code "29") (name "/PB2") (class "Default")
      (node (ref "R37") (pin "2") (pinfunction "2_2") (pintype "passive"))
      (node (ref "R7") (pin "2") (pinfunction "2_2") (pintype "passive"))
      (node (ref "U1") (pin "20") (pinfunction "PB2/AIN2[TIM1_CH3N]_20") (pintype "passive"))
    )
    (net (code "30") (name "/PB3") (class "Default")
      (node (ref "R38") (pin "2") (pinfunction "2_2") (pintype "passive"))
      (node (ref "R8") (pin "2") (pinfunction "2_2") (pintype "passive"))
      (node (ref "U1") (pin "19") (pinfunction "PB3/AIN3[TIM1_ETR]_19") (pintype "passive"))
    )
    (net (code "31") (name "/PB4") (class "Default")
      (node (ref "R9") (pin "2") (pinfunction "2_2") (pintype "passive"))
      (node (ref "U1") (pin "18") (pinfunction "PB4/AIN4[I2C_SCL]_18") (pintype "passive"))
    )
    (net (code "32") (name "/PB5") (class "Default")
      (node (ref "R10") (pin "2") (pinfunction "2_2") (pintype "passive"))
      (node (ref "U1") (pin "17") (pinfunction "PB5/AIN5[I2C_SDA]_17") (pintype "passive"))
    )
    (net (code "33") (name "/PB6") (class "Default")
      (node (ref "R11") (pin "2") (pinfunction "2_2") (pintype "passive"))
      (node (ref "U1") (pin "16") (pinfunction "PB6/AIN6_16") (pintype "passive"))
    )
    (net (code "34") (name "/PB7") (class "Default")
      (node (ref "R12") (pin "2") (pinfunction "2_2") (pintype "passive"))
      (node (ref "U1") (pin "15") (pinfunction "PB7/AIN7_15") (pintype "passive"))
    )
    (net (code "35") (name "/PC0") (class "Default")
      (node (ref "R13") (pin "2") (pinfunction "2_2") (pintype "passive"))
      (node (ref "U1") (pin "26") (pinfunction "PC1/TIM1_CH1_26") (pintype "passive"))
    )
    (net (code "36") (name "/PC1") (class "Default")
      (node (ref "R14") (pin "2") (pinfunction "2_2") (pintype "passive"))
      (node (ref "U1") (pin "27") (pinfunction "PC2/TIM1_CH2_27") (pintype "passive"))
    )
    (net (code "37") (name "/PC2") (class "Default")
      (node (ref "R17") (pin "2") (pinfunction "2_2") (pintype "passive"))
      (node (ref "U1") (pin "28") (pinfunction "PC3/TIM1_CH3_28") (pintype "passive"))
    )
    (net (code "38") (name "/PC3") (class "Default")
      (node (ref "R18") (pin "2") (pinfunction "2_2") (pintype "passive"))
      (node (ref "U1") (pin "29") (pinfunction "PC4/TIM1_CH4_29") (pintype "passive"))
    )
    (net (code "39") (name "/PC4") (class "Default")
      (node (ref "R19") (pin "2") (pinfunction "2_2") (pintype "passive"))
      (node (ref "U1") (pin "30") (pinfunction "PC5/SPI_SCK_30") (pintype "passive"))
    )
    (net (code "40") (name "/PC5") (class "Default")
      (node (ref "R20") (pin "2") (pinfunction "2_2") (pintype "passive"))
      (node (ref "U1") (pin "33") (pinfunction "PC6/SPI_MOSI_33") (pintype "passive"))
    )
    (net (code "41") (name "/PC6") (class "Default")
      (node (ref "R21") (pin "2") (pinfunction "2_2") (pintype "passive"))
      (node (ref "U1") (pin "34") (pinfunction "PC7/SPI_MISO_34") (pintype "passive"))
    )
    (net (code "42") (name "/PD0") (class "Default")
      (node (ref "JP500") (pin "8") (pinfunction "8_8") (pintype "passive"))
      (node (ref "U1") (pin "41") (pinfunction "PD0/TIM3_CH2[TIM1_BKIN/CLK_CCO]_41") (pintype "passive"))
    )
    (net (code "43") (name "/PD1") (class "Default")
      (node (ref "JP3") (pin "3") (pinfunction "SWIM_3") (pintype "passive"))
      (node (ref "U1") (pin "42") (pinfunction "PD1/SWIM_42") (pintype "passive"))
    )
    (net (code "44") (name "/PD2") (class "Default")
      (node (ref "R1") (pin "2") (pinfunction "2_2") (pintype "passive"))
      (node (ref "U1") (pin "43") (pinfunction "PD2/TIM3_CH1[TIM2_CH3]_43") (pintype "passive"))
    )
    (net (code "45") (name "/PD3") (class "Default")
      (node (ref "R2") (pin "2") (pinfunction "2_2") (pintype "passive"))
      (node (ref "U1") (pin "44") (pinfunction "PD3/TIM2_CH2[ADC_ETR]_44") (pintype "passive"))
    )
    (net (code "46") (name "/PD4") (class "Default")
      (node (ref "R3") (pin "2") (pinfunction "2_2") (pintype "passive"))
      (node (ref "U1") (pin "45") (pinfunction "PD4/TIM2_CH1/[BEEP]_45") (pintype "passive"))
    )
    (net (code "47") (name "/PD5") (class "Default")
      (node (ref "R4") (pin "2") (pinfunction "2_2") (pintype "passive"))
      (node (ref "U1") (pin "46") (pinfunction "PD5/UART3_TX_46") (pintype "passive"))
    )
    (net (code "48") (name "/PD6") (class "Default")
      (node (ref "Q6") (pin "3") (pinfunction "C_3") (pintype "passive"))
      (node (ref "R30") (pin "2") (pinfunction "2_2") (pintype "passive"))
      (node (ref "U1") (pin "47") (pinfunction "PD6/UART3_RX_47") (pintype "passive"))
    )
    (net (code "49") (name "/PD7") (class "Default")
      (node (ref "D2") (pin "2") (pinfunction "K_2") (pintype "passive"))
      (node (ref "R32") (pin "1") (pinfunction "1_1") (pintype "passive"))
      (node (ref "U1") (pin "48") (pinfunction "PD7/TLI_48") (pintype "passive"))
    )
    (net (code "50") (name "/PE0") (class "Default")
      (node (ref "R25") (pin "2") (pinfunction "2_2") (pintype "passive"))
      (node (ref "U1") (pin "40") (pinfunction "PE0/CLK_CCO_40") (pintype "passive"))
    )
    (net (code "51") (name "/PE1") (class "Default")
      (node (ref "R15") (pin "2") (pinfunction "2_2") (pintype "passive"))
      (node (ref "U1") (pin "39") (pinfunction "PE1/I2C_SCL_39") (pintype "passive"))
      (node (ref "U2") (pin "6") (pinfunction "SCL_6") (pintype "input"))
    )
    (net (code "52") (name "/PE2") (class "Default")
      (node (ref "R16") (pin "2") (pinfunction "2_2") (pintype "passive"))
      (node (ref "U1") (pin "38") (pinfunction "PE2/I2C_SDA_38") (pintype "passive"))
      (node (ref "U2") (pin "5") (pinfunction "SDA_5") (pintype "bidirectional"))
    )
    (net (code "53") (name "/PE3") (class "Default")
      (node (ref "R26") (pin "2") (pinfunction "2_2") (pintype "passive"))
      (node (ref "U1") (pin "37") (pinfunction "PE3/TIM1_BKIN_37") (pintype "passive"))
    )
    (net (code "54") (name "/PE5") (class "Default")
      (node (ref "R27") (pin "2") (pinfunction "2_2") (pintype "passive"))
      (node (ref "U1") (pin "25") (pinfunction "PE5/SPI_NSS_25") (pintype "passive"))
    )
    (net (code "55") (name "/PE6") (class "Default")
      (node (ref "JP500") (pin "5") (pinfunction "5_5") (pintype "passive"))
      (node (ref "U1") (pin "24") (pinfunction "PE6/AIN9_24") (pintype "passive"))
    )
    (net (code "56") (name "/PE7") (class "Default")
      (node (ref "JP500") (pin "6") (pinfunction "6_6") (pintype "passive"))
      (node (ref "U1") (pin "23") (pinfunction "PE7/AIN8_23") (pintype "passive"))
    )
    (net (code "57") (name "/PG0") (class "Default")
      (node (ref "R22") (pin "2") (pinfunction "2_2") (pintype "passive"))
      (node (ref "U1") (pin "35") (pinfunction "PG0_35") (pintype "passive"))
    )
    (net (code "58") (name "/PG1") (class "Default")
      (node (ref "R39") (pin "2") (pinfunction "2_2") (pintype "passive"))
      (node (ref "U1") (pin "36") (pinfunction "PG1_36") (pintype "passive"))
    )
    (net (code "59") (name "/RST") (class "Default")
      (node (ref "JP3") (pin "4") (pinfunction "RST_4") (pintype "passive"))
      (node (ref "U1") (pin "1") (pinfunction "~{RST}_1") (pintype "passive"))
    )
    (net (code "60") (name "/XT1") (class "Default")
      (node (ref "C13") (pin "2") (pinfunction "2_2") (pintype "passive"))
      (node (ref "U1") (pin "2") (pinfunction "PA1/OSCIN_2") (pintype "passive"))
      (node (ref "Y2") (pin "2") (pinfunction "OSC2_2") (pintype "passive"))
    )
    (net (code "61") (name "/XT2") (class "Default")
      (node (ref "C12") (pin "2") (pinfunction "2_2") (pintype "passive"))
      (node (ref "U1") (pin "3") (pinfunction "PA2/OSCOUT_3") (pintype "passive"))
      (node (ref "Y2") (pin "1") (pinfunction "OSC1_1") (pintype "passive"))
    )
    (net (code "62") (name "GND") (class "Default")
      (node (ref "BT1") (pin "2") (pinfunction "-_2") (pintype "passive"))
      (node (ref "C1") (pin "1") (pinfunction "1_1") (pintype "passive"))
      (node (ref "C10") (pin "2") (pinfunction "2_2") (pintype "passive"))
      (node (ref "C11") (pin "2") (pinfunction "2_2") (pintype "passive"))
      (node (ref "C12") (pin "1") (pinfunction "1_1") (pintype "passive"))
      (node (ref "C13") (pin "1") (pinfunction "1_1") (pintype "passive"))
      (node (ref "C14") (pin "1") (pinfunction "1_1") (pintype "passive"))
      (node (ref "C2") (pin "1") (pinfunction "1_1") (pintype "passive"))
      (node (ref "C4") (pin "2") (pinfunction "2_2") (pintype "passive"))
      (node (ref "C6") (pin "2") (pinfunction "2_2") (pintype "passive"))
      (node (ref "C7") (pin "1") (pinfunction "1_1") (pintype "passive"))
      (node (ref "C8") (pin "1") (pinfunction "1_1") (pintype "passive"))
      (node (ref "C9") (pin "1") (pinfunction "1_1") (pintype "passive"))
      (node (ref "D2") (pin "1") (pinfunction "A_1") (pintype "passive"))
      (node (ref "D4") (pin "1") (pinfunction "A_1") (pintype "passive"))
      (node (ref "JP3") (pin "5") (pinfunction "GND_5") (pintype "passive"))
      (node (ref "JP4") (pin "2") (pinfunction "2_2") (pintype "passive"))
      (node (ref "JP500") (pin "10") (pinfunction "10_10") (pintype "passive"))
      (node (ref "JP500") (pin "9") (pinfunction "9_9") (pintype "passive"))
      (node (ref "JP7") (pin "3") (pinfunction "3_3") (pintype "passive"))
      (node (ref "JP8") (pin "3") (pinfunction "3_3") (pintype "passive"))
      (node (ref "Q6") (pin "2") (pinfunction "E_2") (pintype "passive"))
      (node (ref "R34") (pin "2") (pinfunction "2_2") (pintype "passive"))
      (node (ref "S1") (pin "2") (pinfunction "2_2") (pintype "passive"))
      (node (ref "S2") (pin "2") (pinfunction "2_2") (pintype "passive"))
      (node (ref "S3") (pin "2") (pinfunction "2_2") (pintype "passive"))
      (node (ref "S4") (pin "2") (pinfunction "2_2") (pintype "passive"))
      (node (ref "U1") (pin "14") (pinfunction "Vssa_14") (pintype "passive"))
      (node (ref "U1") (pin "31") (pinfunction "Vssio_31") (pintype "passive"))
      (node (ref "U1") (pin "4") (pinfunction "Vssio_4") (pintype "passive"))
      (node (ref "U1") (pin "5") (pinfunction "Vss_5") (pintype "passive"))
      (node (ref "U2") (pin "4") (pinfunction "GND_4") (pintype "power_in"))
      (node (ref "U8") (pin "4") (pinfunction "GND_4") (pintype "power_in"))
    )
    (net (code "63") (name "Net-(A1-Pad2)") (class "Default")
      (node (ref "A1") (pin "2") (pinfunction "2_2") (pintype "passive"))
      (node (ref "R39") (pin "1") (pinfunction "1_1") (pintype "passive"))
    )
    (net (code "64") (name "Net-(BT1-+)") (class "Default")
      (node (ref "BT1") (pin "1") (pinfunction "+_1") (pintype "passive"))
      (node (ref "U2") (pin "3") (pinfunction "VBAT_3") (pintype "power_in"))
    )
    (net (code "65") (name "Net-(C10-Pad1)") (class "Default")
      (node (ref "C10") (pin "1") (pinfunction "1_1") (pintype "passive"))
      (node (ref "JP7") (pin "1") (pinfunction "1_1") (pintype "passive"))
      (node (ref "R28") (pin "1") (pinfunction "1_1") (pintype "passive"))
    )
    (net (code "66") (name "Net-(C11-Pad1)") (class "Default")
      (node (ref "C11") (pin "1") (pinfunction "1_1") (pintype "passive"))
      (node (ref "JP8") (pin "1") (pinfunction "1_1") (pintype "passive"))
      (node (ref "R31") (pin "1") (pinfunction "1_1") (pintype "passive"))
    )
    (net (code "67") (name "Net-(D1-A)") (class "Default")
      (node (ref "D1") (pin "1") (pinfunction "A_1") (pintype "passive"))
      (node (ref "JP4") (pin "1") (pinfunction "1_1") (pintype "passive"))
    )
    (net (code "68") (name "Net-(D3-A)") (class "Default")
      (node (ref "D3") (pin "1") (pinfunction "A_1") (pintype "passive"))
      (node (ref "JP500") (pin "2") (pinfunction "2_2") (pintype "passive"))
    )
    (net (code "69") (name "Net-(JP5-Pad1)") (class "Default")
      (node (ref "JP5") (pin "1") (pinfunction "1_1") (pintype "passive"))
      (node (ref "U5") (pin "6") (pinfunction "A/K_6") (pintype "passive"))
      (node (ref "U6") (pin "6") (pinfunction "A/K_6") (pintype "passive"))
      (node (ref "U7") (pin "6") (pinfunction "A/K_6") (pintype "passive"))
    )
    (net (code "70") (name "Net-(JP5-Pad2)") (class "Default")
      (node (ref "JP5") (pin "2") (pinfunction "2_2") (pintype "passive"))
      (node (ref "U5") (pin "4") (pinfunction "A/K_4") (pintype "passive"))
    )
    (net (code "71") (name "Net-(JP6-Pad1)") (class "Default")
      (node (ref "JP6") (pin "1") (pinfunction "1_1") (pintype "passive"))
      (node (ref "U6") (pin "4") (pinfunction "A/K_4") (pintype "passive"))
    )
    (net (code "72") (name "Net-(JP6-Pad2)") (class "Default")
      (node (ref "JP6") (pin "2") (pinfunction "2_2") (pintype "passive"))
      (node (ref "U7") (pin "4") (pinfunction "A/K_4") (pintype "passive"))
    )
    (net (code "73") (name "Net-(JP7-Pad2)") (class "Default")
      (node (ref "JP7") (pin "2") (pinfunction "2_2") (pintype "passive"))
      (node (ref "R29") (pin "2") (pinfunction "2_2") (pintype "passive"))
      (node (ref "R32") (pin "2") (pinfunction "2_2") (pintype "passive"))
    )
    (net (code "74") (name "Net-(JP8-Pad2)") (class "Default")
      (node (ref "JP8") (pin "2") (pinfunction "2_2") (pintype "passive"))
      (node (ref "R33") (pin "2") (pinfunction "2_2") (pintype "passive"))
    )
    (net (code "75") (name "Net-(Q1-B)") (class "Default")
      (node (ref "Q1") (pin "1") (pinfunction "B_1") (pintype "passive"))
      (node (ref "R1") (pin "1") (pinfunction "1_1") (pintype "passive"))
    )
    (net (code "76") (name "Net-(Q2-B)") (class "Default")
      (node (ref "Q2") (pin "1") (pinfunction "B_1") (pintype "passive"))
      (node (ref "R2") (pin "1") (pinfunction "1_1") (pintype "passive"))
    )
    (net (code "77") (name "Net-(Q3-B)") (class "Default")
      (node (ref "Q3") (pin "1") (pinfunction "B_1") (pintype "passive"))
      (node (ref "R3") (pin "1") (pinfunction "1_1") (pintype "passive"))
    )
    (net (code "78") (name "Net-(Q4-B)") (class "Default")
      (node (ref "Q4") (pin "1") (pinfunction "B_1") (pintype "passive"))
      (node (ref "R4") (pin "1") (pinfunction "1_1") (pintype "passive"))
    )
    (net (code "79") (name "Net-(Q6-B)") (class "Default")
      (node (ref "Q6") (pin "1") (pinfunction "B_1") (pintype "passive"))
      (node (ref "R33") (pin "1") (pinfunction "1_1") (pintype "passive"))
      (node (ref "R34") (pin "1") (pinfunction "1_1") (pintype "passive"))
    )
    (net (code "80") (name "Net-(R35-Pad1)") (class "Default")
      (node (ref "R35") (pin "1") (pinfunction "1_1") (pintype "passive"))
      (node (ref "S1") (pin "1") (pinfunction "1_1") (pintype "passive"))
    )
    (net (code "81") (name "Net-(R36-Pad1)") (class "Default")
      (node (ref "R36") (pin "1") (pinfunction "1_1") (pintype "passive"))
      (node (ref "S2") (pin "1") (pinfunction "1_1") (pintype "passive"))
    )
    (net (code "82") (name "Net-(R37-Pad1)") (class "Default")
      (node (ref "R37") (pin "1") (pinfunction "1_1") (pintype "passive"))
      (node (ref "S3") (pin "1") (pinfunction "1_1") (pintype "passive"))
    )
    (net (code "83") (name "Net-(R38-Pad1)") (class "Default")
      (node (ref "R38") (pin "1") (pinfunction "1_1") (pintype "passive"))
      (node (ref "S4") (pin "1") (pinfunction "1_1") (pintype "passive"))
    )
    (net (code "84") (name "Net-(U1-VCAP)") (class "Default")
      (node (ref "C14") (pin "2") (pinfunction "2_2") (pintype "passive"))
      (node (ref "U1") (pin "6") (pinfunction "VCAP_6") (pintype "passive"))
    )
    (net (code "85") (name "Net-(U2-X1)") (class "Default")
      (node (ref "C1") (pin "2") (pinfunction "2_2") (pintype "passive"))
      (node (ref "U2") (pin "1") (pinfunction "X1_1") (pintype "input"))
      (node (ref "Y1") (pin "1") (pinfunction "OSC1_1") (pintype "passive"))
    )
    (net (code "86") (name "Net-(U2-X2)") (class "Default")
      (node (ref "C2") (pin "2") (pinfunction "2_2") (pintype "passive"))
      (node (ref "U2") (pin "2") (pinfunction "X2_2") (pintype "input"))
      (node (ref "Y1") (pin "2") (pinfunction "OSC2_2") (pintype "passive"))
    )
    (net (code "87") (name "Net-(U5-K)") (class "Default")
      (node (ref "R25") (pin "1") (pinfunction "1_1") (pintype "passive"))
      (node (ref "U5") (pin "2") (pinfunction "K_2") (pintype "passive"))
    )
    (net (code "88") (name "Net-(U6-K)") (class "Default")
      (node (ref "R26") (pin "1") (pinfunction "1_1") (pintype "passive"))
      (node (ref "U6") (pin "2") (pinfunction "K_2") (pintype "passive"))
    )
    (net (code "89") (name "Net-(U7-K)") (class "Default")
      (node (ref "R27") (pin "1") (pinfunction "1_1") (pintype "passive"))
      (node (ref "U7") (pin "2") (pinfunction "K_2") (pintype "passive"))
    )
    (net (code "90") (name "unconnected-(U2-SQW{slash}OUT-Pad7)") (class "Default")
      (node (ref "U2") (pin "7") (pinfunction "SQW/OUT_7") (pintype "output"))
    )
  )
)
